# MOTOR.net
KiCad netlist of a schematic drawn in Altium Designer
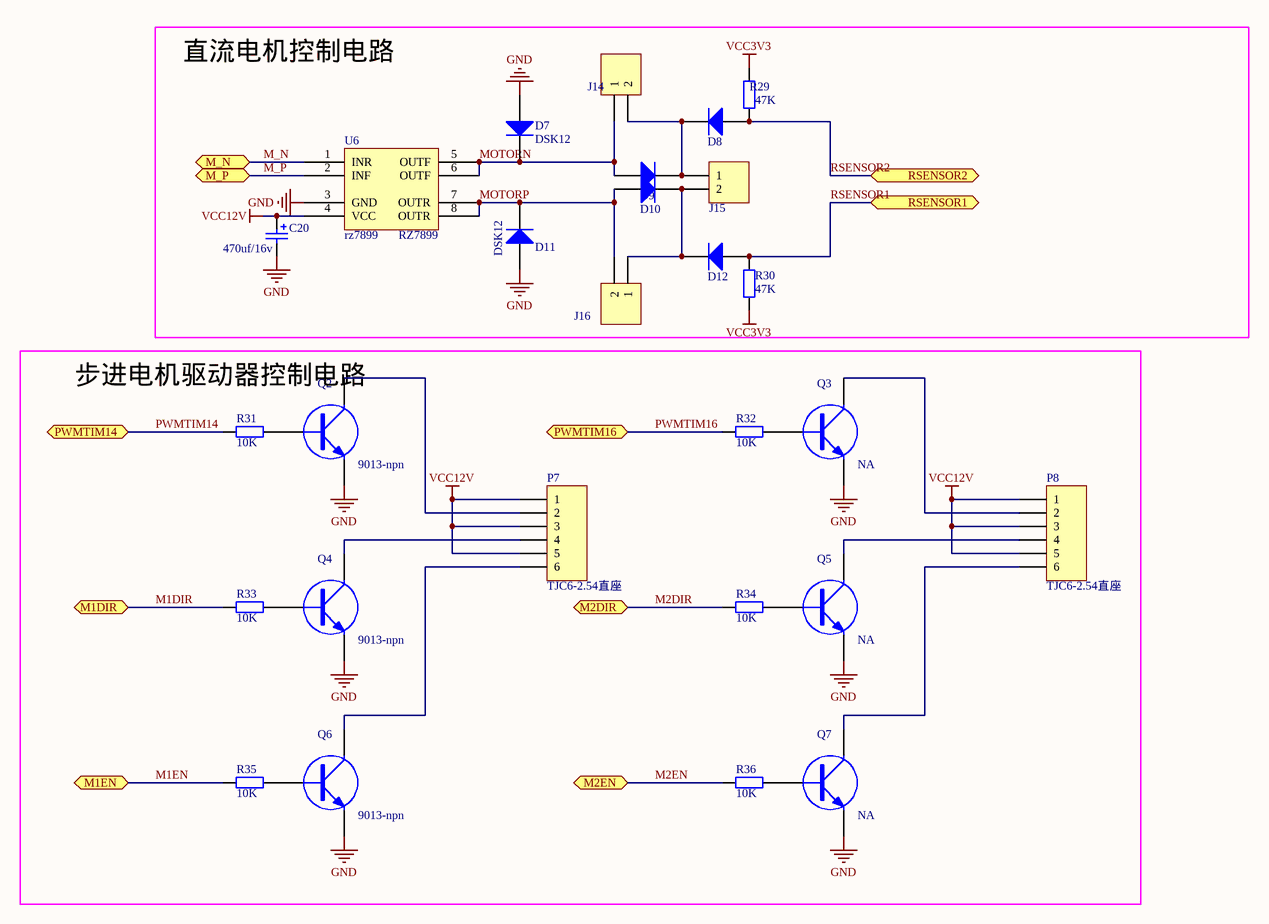
[diagram p0: MOTOR.SchDoc]

(export (version "E")
  (design (tool "Eeschema 10.0.6"))
  (components
    (comp (ref "C20")
      (value "470uf/16v")
      (footprint "cap_470/16v")
      (description "Polarized Capacitor (Radial)")
      (libsource (lib "阻容晶体管元件") (part "Cap_直插470uf/16v"))
    )
    (comp (ref "D7")
      (value "Diode_SOD523")
      (footprint "SOD123_D")
      (description "Default Diode")
      (fields (field (name "型号") "DSK12"))
      (libsource (lib "阻容晶体管元件") (part "Diode_SOD523"))
    )
    (comp (ref "D8")
      (value "Diode_SOD323")
      (footprint "SOD323_D")
      (description "Default Diode")
      (fields (field (name "PUBLISHER") "Altium Limited"))
      (libsource (lib "阻容晶体管元件") (part "Diode_SOD323"))
    )
    (comp (ref "D9")
      (value "Diode_DO214AB")
      (footprint "SOD123-F")
      (description "Default Diode")
      (fields (field (name "PUBLISHER") "Altium Limited"))
      (libsource (lib "阻容晶体管元件") (part "Diode_DO214AB"))
    )
    (comp (ref "D10")
      (value "Diode_DO214AB")
      (footprint "SOD123-F")
      (description "Default Diode")
      (fields (field (name "PUBLISHER") "Altium Limited"))
      (libsource (lib "阻容晶体管元件") (part "Diode_DO214AB"))
    )
    (comp (ref "D11")
      (value "Diode_SOD523")
      (footprint "SOD123_D")
      (description "Default Diode")
      (fields (field (name "型号") "DSK12"))
      (libsource (lib "阻容晶体管元件") (part "Diode_SOD523"))
    )
    (comp (ref "D12")
      (value "Diode_SOD323")
      (footprint "SOD323_D")
      (description "Default Diode")
      (fields (field (name "PUBLISHER") "Altium Limited"))
      (libsource (lib "阻容晶体管元件") (part "Diode_SOD323"))
    )
    (comp (ref "J14")
      (value "XHB2.54-2PIN-带锁扣")
      (footprint "SIP2")
      (description "Header, 4-Pin")
      (libsource (lib "") (part "XHB2.54-2P直座_1"))
    )
    (comp (ref "J15")
      (value "XHB2.54-2PIN-带锁扣")
      (footprint "SIP2")
      (description "Header, 4-Pin")
      (libsource (lib "接插件") (part "XHB2.54-2P直座"))
    )
    (comp (ref "J16")
      (value "XHB2.54-2PIN-带锁扣")
      (footprint "SIP2")
      (description "Header, 4-Pin")
      (libsource (lib "") (part "XHB2.54-2P直座_2"))
    )
    (comp (ref "P7")
      (value "TJC6-2.54直座")
      (footprint "SIP6")
      (description "Header, 6-Pin")
      (libsource (lib "接插件") (part "TJC6-2.54直座"))
    )
    (comp (ref "P8")
      (value "TJC6-2.54直座")
      (footprint "SIP6")
      (description "Header, 6-Pin")
      (libsource (lib "接插件") (part "TJC6-2.54直座"))
    )
    (comp (ref "Q2")
      (value "NPN_SOT23")
      (footprint "SOT23")
      (description "NPN Bipolar Transistor")
      (fields (field (name "型号") "9013-npn"))
      (libsource (lib "阻容晶体管元件") (part "NPN_SOT23"))
    )
    (comp (ref "Q3")
      (value "NPN_SOT23")
      (footprint "SOT23")
      (description "NPN Bipolar Transistor")
      (fields (field (name "型号") "NA"))
      (libsource (lib "阻容晶体管元件") (part "NPN_SOT23"))
    )
    (comp (ref "Q4")
      (value "NPN_SOT23")
      (footprint "SOT23")
      (description "NPN Bipolar Transistor")
      (fields (field (name "型号") "9013-npn"))
      (libsource (lib "阻容晶体管元件") (part "NPN_SOT23"))
    )
    (comp (ref "Q5")
      (value "NPN_SOT23")
      (footprint "SOT23")
      (description "NPN Bipolar Transistor")
      (fields (field (name "型号") "NA"))
      (libsource (lib "阻容晶体管元件") (part "NPN_SOT23"))
    )
    (comp (ref "Q6")
      (value "NPN_SOT23")
      (footprint "SOT23")
      (description "NPN Bipolar Transistor")
      (fields (field (name "型号") "9013-npn"))
      (libsource (lib "阻容晶体管元件") (part "NPN_SOT23"))
    )
    (comp (ref "Q7")
      (value "NPN_SOT23")
      (footprint "SOT23")
      (description "NPN Bipolar Transistor")
      (fields (field (name "型号") "NA"))
      (libsource (lib "阻容晶体管元件") (part "NPN_SOT23"))
    )
    (comp (ref "R29")
      (value "Res_0603")
      (footprint "0603R")
      (description "Resistor")
      (fields (field (name "型号") "47K"))
      (libsource (lib "") (part "Res_0603_1"))
    )
    (comp (ref "R30")
      (value "Res_0603")
      (footprint "0603R")
      (description "Resistor")
      (fields (field (name "型号") "47K"))
      (libsource (lib "") (part "Res_0603_1"))
    )
    (comp (ref "R31")
      (value "Res_0603")
      (footprint "0603R")
      (description "Resistor")
      (fields (field (name "型号") "10K"))
      (libsource (lib "阻容晶体管元件") (part "Res_0603"))
    )
    (comp (ref "R32")
      (value "Res_0603")
      (footprint "0603R")
      (description "Resistor")
      (fields (field (name "型号") "10K"))
      (libsource (lib "阻容晶体管元件") (part "Res_0603"))
    )
    (comp (ref "R33")
      (value "Res_0603")
      (footprint "0603R")
      (description "Resistor")
      (fields (field (name "型号") "10K"))
      (libsource (lib "阻容晶体管元件") (part "Res_0603"))
    )
    (comp (ref "R34")
      (value "Res_0603")
      (footprint "0603R")
      (description "Resistor")
      (fields (field (name "型号") "10K"))
      (libsource (lib "阻容晶体管元件") (part "Res_0603"))
    )
    (comp (ref "R35")
      (value "Res_0603")
      (footprint "0603R")
      (description "Resistor")
      (fields (field (name "型号") "10K"))
      (libsource (lib "阻容晶体管元件") (part "Res_0603"))
    )
    (comp (ref "R36")
      (value "Res_0603")
      (footprint "0603R")
      (description "Resistor")
      (fields (field (name "型号") "10K"))
      (libsource (lib "阻容晶体管元件") (part "Res_0603"))
    )
    (comp (ref "U6")
      (value "rz7899")
      (footprint "SOP_8")
      (description "电机驱动芯片3-25V 5A")
      (fields (field (name "型号") "RZ7899"))
      (libsource (lib "Schlib") (part "rz7899"))
    )
  )
  (nets
    (net (code "1") (name "/M1DIR") (class "Default")
      (node (ref "R33") (pin "1") (pinfunction "1_1") (pintype "passive"))
    )
    (net (code "2") (name "/M1EN") (class "Default")
      (node (ref "R35") (pin "1") (pinfunction "1_1") (pintype "passive"))
    )
    (net (code "3") (name "/M2DIR") (class "Default")
      (node (ref "R34") (pin "1") (pinfunction "1_1") (pintype "passive"))
    )
    (net (code "4") (name "/M2EN") (class "Default")
      (node (ref "R36") (pin "1") (pinfunction "1_1") (pintype "passive"))
    )
    (net (code "5") (name "/MOTORN") (class "Default")
      (node (ref "D7") (pin "2") (pinfunction "2_2") (pintype "passive"))
      (node (ref "D9") (pin "1") (pinfunction "1_1") (pintype "passive"))
      (node (ref "J14") (pin "1") (pinfunction "1_1") (pintype "passive"))
      (node (ref "U6") (pin "5") (pinfunction "OUTF_5") (pintype "passive"))
      (node (ref "U6") (pin "6") (pinfunction "OUTF_6") (pintype "passive"))
    )
    (net (code "6") (name "/MOTORP") (class "Default")
      (node (ref "D10") (pin "1") (pinfunction "1_1") (pintype "passive"))
      (node (ref "D11") (pin "2") (pinfunction "2_2") (pintype "passive"))
      (node (ref "J16") (pin "2") (pinfunction "2_2") (pintype "passive"))
      (node (ref "U6") (pin "7") (pinfunction "OUTR_7") (pintype "passive"))
      (node (ref "U6") (pin "8") (pinfunction "OUTR_8") (pintype "passive"))
    )
    (net (code "7") (name "/M_N") (class "Default")
      (node (ref "U6") (pin "1") (pinfunction "INR_1") (pintype "passive"))
    )
    (net (code "8") (name "/M_P") (class "Default")
      (node (ref "U6") (pin "2") (pinfunction "INF_2") (pintype "passive"))
    )
    (net (code "9") (name "/PWMTIM14") (class "Default")
      (node (ref "R31") (pin "1") (pinfunction "1_1") (pintype "passive"))
    )
    (net (code "10") (name "/PWMTIM16") (class "Default")
      (node (ref "R32") (pin "1") (pinfunction "1_1") (pintype "passive"))
    )
    (net (code "11") (name "/RSENSOR1") (class "Default")
      (node (ref "D12") (pin "1") (pinfunction "1_1") (pintype "passive"))
      (node (ref "R30") (pin "2") (pinfunction "2_2") (pintype "passive"))
    )
    (net (code "12") (name "/RSENSOR2") (class "Default")
      (node (ref "D8") (pin "1") (pinfunction "1_1") (pintype "passive"))
      (node (ref "R29") (pin "1") (pinfunction "1_1") (pintype "passive"))
    )
    (net (code "13") (name "GND") (class "Default")
      (node (ref "C20") (pin "2") (pinfunction "2_2") (pintype "passive"))
      (node (ref "D11") (pin "1") (pinfunction "1_1") (pintype "passive"))
      (node (ref "D7") (pin "1") (pinfunction "1_1") (pintype "passive"))
      (node (ref "Q2") (pin "2") (pinfunction "E_2") (pintype "passive"))
      (node (ref "Q3") (pin "2") (pinfunction "E_2") (pintype "passive"))
      (node (ref "Q4") (pin "2") (pinfunction "E_2") (pintype "passive"))
      (node (ref "Q5") (pin "2") (pinfunction "E_2") (pintype "passive"))
      (node (ref "Q6") (pin "2") (pinfunction "E_2") (pintype "passive"))
      (node (ref "Q7") (pin "2") (pinfunction "E_2") (pintype "passive"))
      (node (ref "U6") (pin "3") (pinfunction "GND_3") (pintype "passive"))
    )
    (net (code "14") (name "Net-(D8-Pad2)") (class "Default")
      (node (ref "D8") (pin "2") (pinfunction "2_2") (pintype "passive"))
      (node (ref "D9") (pin "2") (pinfunction "2_2") (pintype "passive"))
      (node (ref "J14") (pin "2") (pinfunction "2_2") (pintype "passive"))
      (node (ref "J15") (pin "1") (pinfunction "1_1") (pintype "passive"))
    )
    (net (code "15") (name "Net-(D10-Pad2)") (class "Default")
      (node (ref "D10") (pin "2") (pinfunction "2_2") (pintype "passive"))
      (node (ref "D12") (pin "2") (pinfunction "2_2") (pintype "passive"))
      (node (ref "J15") (pin "2") (pinfunction "2_2") (pintype "passive"))
      (node (ref "J16") (pin "1") (pinfunction "1_1") (pintype "passive"))
    )
    (net (code "16") (name "Net-(Q2-B)") (class "Default")
      (node (ref "Q2") (pin "1") (pinfunction "B_1") (pintype "passive"))
      (node (ref "R31") (pin "2") (pinfunction "2_2") (pintype "passive"))
    )
    (net (code "17") (name "Net-(Q2-C)") (class "Default")
      (node (ref "P7") (pin "2") (pinfunction "2_2") (pintype "passive"))
      (node (ref "Q2") (pin "3") (pinfunction "C_3") (pintype "passive"))
    )
    (net (code "18") (name "Net-(Q3-B)") (class "Default")
      (node (ref "Q3") (pin "1") (pinfunction "B_1") (pintype "passive"))
      (node (ref "R32") (pin "2") (pinfunction "2_2") (pintype "passive"))
    )
    (net (code "19") (name "Net-(Q3-C)") (class "Default")
      (node (ref "P8") (pin "2") (pinfunction "2_2") (pintype "passive"))
      (node (ref "Q3") (pin "3") (pinfunction "C_3") (pintype "passive"))
    )
    (net (code "20") (name "Net-(Q4-B)") (class "Default")
      (node (ref "Q4") (pin "1") (pinfunction "B_1") (pintype "passive"))
      (node (ref "R33") (pin "2") (pinfunction "2_2") (pintype "passive"))
    )
    (net (code "21") (name "Net-(Q4-C)") (class "Default")
      (node (ref "P7") (pin "4") (pinfunction "4_4") (pintype "passive"))
      (node (ref "Q4") (pin "3") (pinfunction "C_3") (pintype "passive"))
    )
    (net (code "22") (name "Net-(Q5-B)") (class "Default")
      (node (ref "Q5") (pin "1") (pinfunction "B_1") (pintype "passive"))
      (node (ref "R34") (pin "2") (pinfunction "2_2") (pintype "passive"))
    )
    (net (code "23") (name "Net-(Q5-C)") (class "Default")
      (node (ref "P8") (pin "4") (pinfunction "4_4") (pintype "passive"))
      (node (ref "Q5") (pin "3") (pinfunction "C_3") (pintype "passive"))
    )
    (net (code "24") (name "Net-(Q6-B)") (class "Default")
      (node (ref "Q6") (pin "1") (pinfunction "B_1") (pintype "passive"))
      (node (ref "R35") (pin "2") (pinfunction "2_2") (pintype "passive"))
    )
    (net (code "25") (name "Net-(Q6-C)") (class "Default")
      (node (ref "P7") (pin "6") (pinfunction "6_6") (pintype "passive"))
      (node (ref "Q6") (pin "3") (pinfunction "C_3") (pintype "passive"))
    )
    (net (code "26") (name "Net-(Q7-B)") (class "Default")
      (node (ref "Q7") (pin "1") (pinfunction "B_1") (pintype "passive"))
      (node (ref "R36") (pin "2") (pinfunction "2_2") (pintype "passive"))
    )
    (net (code "27") (name "Net-(Q7-C)") (class "Default")
      (node (ref "P8") (pin "6") (pinfunction "6_6") (pintype "passive"))
      (node (ref "Q7") (pin "3") (pinfunction "C_3") (pintype "passive"))
    )
    (net (code "28") (name "VCC3V3") (class "Default")
      (node (ref "R29") (pin "2") (pinfunction "2_2") (pintype "passive"))
      (node (ref "R30") (pin "1") (pinfunction "1_1") (pintype "passive"))
    )
    (net (code "29") (name "VCC12V") (class "Default")
      (node (ref "C20") (pin "1") (pinfunction "1_1") (pintype "passive"))
      (node (ref "P7") (pin "1") (pinfunction "1_1") (pintype "passive"))
      (node (ref "P7") (pin "3") (pinfunction "3_3") (pintype "passive"))
      (node (ref "P7") (pin "5") (pinfunction "5_5") (pintype "passive"))
      (node (ref "P8") (pin "1") (pinfunction "1_1") (pintype "passive"))
      (node (ref "P8") (pin "3") (pinfunction "3_3") (pintype "passive"))
      (node (ref "P8") (pin "5") (pinfunction "5_5") (pintype "passive"))
      (node (ref "U6") (pin "4") (pinfunction "VCC_4") (pintype "passive"))
    )
  )
)
